# HW2.net
KiCad netlist of a schematic drawn in EAGLE
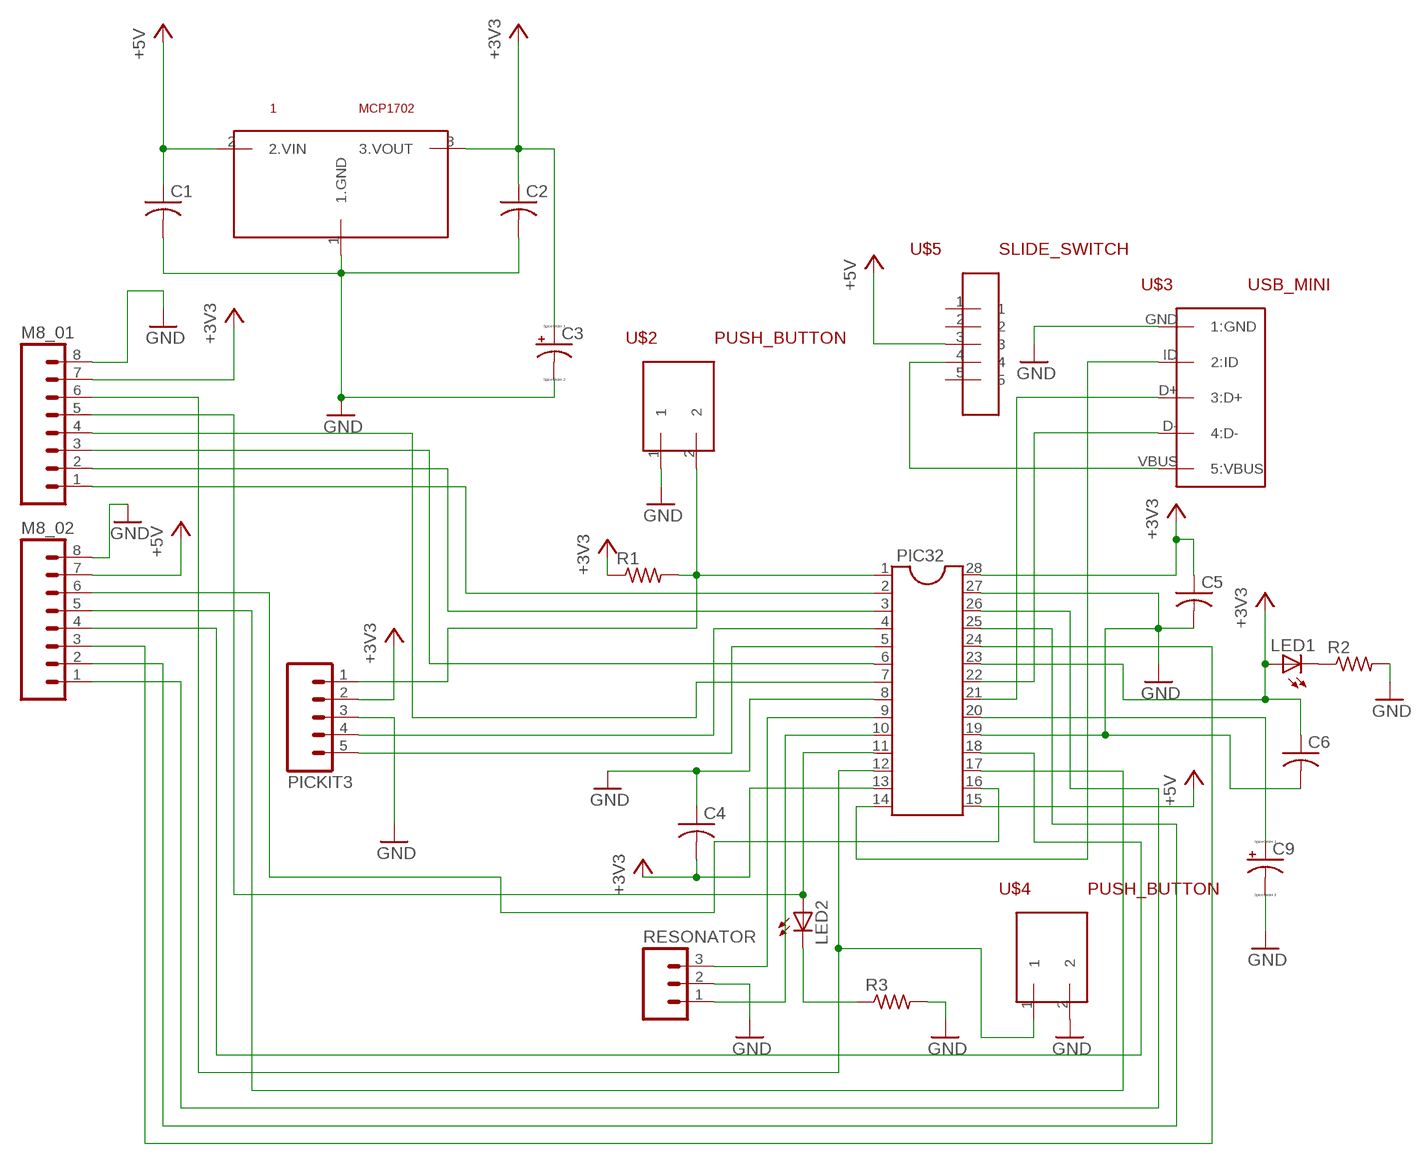
[diagram p0: schematic, sheet 1]

(export (version "E")
  (design (tool "Eeschema 10.0.6"))
  (components
    (comp (ref "1")
      (value "MCP1702")
      (footprint "eagle-import:TO92")
      (libsource (lib "eagle-import") (part "MCP1702"))
    )
    (comp (ref "C1")
      (value "C-US025-025X050")
      (footprint "eagle-import:C025-025X050")
      (libsource (lib "eagle-import") (part "C-US025-025X050"))
    )
    (comp (ref "C2")
      (value "C-US025-025X050")
      (footprint "eagle-import:C025-025X050")
      (libsource (lib "eagle-import") (part "C-US025-025X050"))
    )
    (comp (ref "C3")
      (value "CPOL-USE5-5")
      (footprint "eagle-import:E5-5")
      (libsource (lib "eagle-import") (part "CPOL-USE5-5"))
    )
    (comp (ref "C4")
      (value "C-US025-025X050")
      (footprint "eagle-import:C025-025X050")
      (libsource (lib "eagle-import") (part "C-US025-025X050"))
    )
    (comp (ref "C5")
      (value "C-US025-025X050")
      (footprint "eagle-import:C025-025X050")
      (libsource (lib "eagle-import") (part "C-US025-025X050"))
    )
    (comp (ref "C6")
      (value "C-US025-025X050")
      (footprint "eagle-import:C025-025X050")
      (libsource (lib "eagle-import") (part "C-US025-025X050"))
    )
    (comp (ref "C9")
      (value "CPOL-USE5-5")
      (footprint "eagle-import:E5-5")
      (libsource (lib "eagle-import") (part "CPOL-USE5-5"))
    )
    (comp (ref "LED1")
      (value "LED3MM")
      (footprint "eagle-import:LED3MM")
      (libsource (lib "eagle-import") (part "LED3MM"))
    )
    (comp (ref "LED2")
      (value "LED3MM")
      (footprint "eagle-import:LED3MM")
      (libsource (lib "eagle-import") (part "LED3MM"))
    )
    (comp (ref "M8_01")
      (value "M08")
      (footprint "eagle-import:1X08_ROUND")
      (libsource (lib "eagle-import") (part "M08"))
    )
    (comp (ref "M8_02")
      (value "M08")
      (footprint "eagle-import:1X08_ROUND")
      (libsource (lib "eagle-import") (part "M08"))
    )
    (comp (ref "PIC32")
      (value "DIL28-3")
      (footprint "eagle-import:DIL28-3")
      (libsource (lib "eagle-import") (part "DIL28-3"))
    )
    (comp (ref "PICKIT3")
      (value "M05PTH")
      (footprint "eagle-import:1X05")
      (libsource (lib "eagle-import") (part "M05PTH"))
    )
    (comp (ref "R1")
      (value "R-US_0207/10")
      (footprint "eagle-import:0207_10")
      (libsource (lib "eagle-import") (part "R-US_0207/10"))
    )
    (comp (ref "R2")
      (value "R-US_0207/10")
      (footprint "eagle-import:0207_10")
      (libsource (lib "eagle-import") (part "R-US_0207/10"))
    )
    (comp (ref "R3")
      (value "R-US_0207/10")
      (footprint "eagle-import:0207_10")
      (libsource (lib "eagle-import") (part "R-US_0207/10"))
    )
    (comp (ref "RESONATOR")
      (value "M03PTH")
      (footprint "eagle-import:1X03")
      (libsource (lib "eagle-import") (part "M03PTH"))
    )
    (comp (ref "U$2")
      (value "PUSH_BUTTON")
      (footprint "eagle-import:1X02_NO_SILK")
      (libsource (lib "eagle-import") (part "PUSH_BUTTON"))
    )
    (comp (ref "U$3")
      (value "USB_MINI")
      (footprint "eagle-import:USB-MB-H")
      (libsource (lib "eagle-import") (part "USB_MINI"))
    )
    (comp (ref "U$4")
      (value "PUSH_BUTTON")
      (footprint "eagle-import:1X02_NO_SILK")
      (libsource (lib "eagle-import") (part "PUSH_BUTTON"))
    )
    (comp (ref "U$5")
      (value "SLIDE_SWITCH")
      (footprint "eagle-import:1X05")
      (libsource (lib "eagle-import") (part "SLIDE_SWITCH"))
    )
  )
  (nets
    (net (code "1") (name "+3V3") (class "Default")
      (node (ref "1") (pin "3") (pinfunction "3.VOUT_3") (pintype "bidirectional"))
      (node (ref "C2") (pin "1") (pinfunction "1_1") (pintype "passive"))
      (node (ref "C3") (pin "+") (pinfunction "+_+") (pintype "passive"))
      (node (ref "C4") (pin "2") (pinfunction "2_2") (pintype "passive"))
      (node (ref "C5") (pin "1") (pinfunction "1_1") (pintype "passive"))
      (node (ref "C6") (pin "1") (pinfunction "1_1") (pintype "passive"))
      (node (ref "LED1") (pin "A") (pinfunction "A_A") (pintype "passive"))
      (node (ref "M8_01") (pin "7") (pinfunction "7_7") (pintype "passive"))
      (node (ref "PIC32") (pin "13") (pinfunction "13_13") (pintype "passive"))
      (node (ref "PIC32") (pin "23") (pinfunction "23_23") (pintype "passive"))
      (node (ref "PIC32") (pin "28") (pinfunction "28_28") (pintype "passive"))
      (node (ref "PICKIT3") (pin "2") (pinfunction "2_2") (pintype "passive"))
      (node (ref "R1") (pin "1") (pinfunction "1_1") (pintype "passive"))
    )
    (net (code "2") (name "+5V") (class "Default")
      (node (ref "1") (pin "2") (pinfunction "2.VIN_2") (pintype "bidirectional"))
      (node (ref "C1") (pin "1") (pinfunction "1_1") (pintype "passive"))
      (node (ref "M8_02") (pin "7") (pinfunction "7_7") (pintype "passive"))
      (node (ref "PIC32") (pin "15") (pinfunction "15_15") (pintype "passive"))
      (node (ref "U$5") (pin "3") (pinfunction "3_3") (pintype "bidirectional"))
    )
    (net (code "3") (name "GND") (class "Default")
      (node (ref "1") (pin "1") (pinfunction "1.GND_1") (pintype "bidirectional"))
      (node (ref "C1") (pin "2") (pinfunction "2_2") (pintype "passive"))
      (node (ref "C2") (pin "2") (pinfunction "2_2") (pintype "passive"))
      (node (ref "C3") (pin "-") (pinfunction "-_-") (pintype "passive"))
      (node (ref "C4") (pin "1") (pinfunction "1_1") (pintype "passive"))
      (node (ref "C5") (pin "2") (pinfunction "2_2") (pintype "passive"))
      (node (ref "C6") (pin "2") (pinfunction "2_2") (pintype "passive"))
      (node (ref "C9") (pin "-") (pinfunction "-_-") (pintype "passive"))
      (node (ref "M8_01") (pin "8") (pinfunction "8_8") (pintype "passive"))
      (node (ref "M8_02") (pin "8") (pinfunction "8_8") (pintype "passive"))
      (node (ref "PIC32") (pin "19") (pinfunction "19_19") (pintype "passive"))
      (node (ref "PIC32") (pin "27") (pinfunction "27_27") (pintype "passive"))
      (node (ref "PIC32") (pin "8") (pinfunction "8_8") (pintype "passive"))
      (node (ref "PICKIT3") (pin "3") (pinfunction "3_3") (pintype "passive"))
      (node (ref "R2") (pin "2") (pinfunction "2_2") (pintype "passive"))
      (node (ref "R3") (pin "2") (pinfunction "2_2") (pintype "passive"))
      (node (ref "RESONATOR") (pin "2") (pinfunction "2_2") (pintype "passive"))
      (node (ref "U$2") (pin "1") (pinfunction "1_1") (pintype "bidirectional"))
      (node (ref "U$3") (pin "GND") (pinfunction "1:GND_GND") (pintype "bidirectional"))
      (node (ref "U$4") (pin "2") (pinfunction "2_2") (pintype "bidirectional"))
    )
    (net (code "4") (name "Net-(C9-Pad+)") (class "Default")
      (node (ref "C9") (pin "+") (pinfunction "+_+") (pintype "passive"))
      (node (ref "PIC32") (pin "20") (pinfunction "20_20") (pintype "passive"))
    )
    (net (code "5") (name "Net-(LED1-C)") (class "Default")
      (node (ref "LED1") (pin "K") (pinfunction "C_K") (pintype "passive"))
      (node (ref "R2") (pin "1") (pinfunction "1_1") (pintype "passive"))
    )
    (net (code "6") (name "Net-(LED2-C)") (class "Default")
      (node (ref "LED2") (pin "K") (pinfunction "C_K") (pintype "passive"))
      (node (ref "R3") (pin "1") (pinfunction "1_1") (pintype "passive"))
    )
    (net (code "7") (name "Net-(LED2-PadA)") (class "Default")
      (node (ref "LED2") (pin "A") (pinfunction "A_A") (pintype "passive"))
      (node (ref "M8_01") (pin "5") (pinfunction "5_5") (pintype "passive"))
      (node (ref "PIC32") (pin "11") (pinfunction "11_11") (pintype "passive"))
    )
    (net (code "8") (name "Net-(M8_01-Pad2)") (class "Default")
      (node (ref "M8_01") (pin "2") (pinfunction "2_2") (pintype "passive"))
      (node (ref "PIC32") (pin "3") (pinfunction "3_3") (pintype "passive"))
    )
    (net (code "9") (name "Net-(M8_01-Pad3)") (class "Default")
      (node (ref "M8_01") (pin "3") (pinfunction "3_3") (pintype "passive"))
      (node (ref "PIC32") (pin "6") (pinfunction "6_6") (pintype "passive"))
    )
    (net (code "10") (name "Net-(M8_01-Pad4)") (class "Default")
      (node (ref "M8_01") (pin "4") (pinfunction "4_4") (pintype "passive"))
      (node (ref "PIC32") (pin "7") (pinfunction "7_7") (pintype "passive"))
    )
    (net (code "11") (name "Net-(M8_01-Pad6)") (class "Default")
      (node (ref "M8_01") (pin "6") (pinfunction "6_6") (pintype "passive"))
      (node (ref "PIC32") (pin "12") (pinfunction "12_12") (pintype "passive"))
      (node (ref "U$4") (pin "1") (pinfunction "1_1") (pintype "bidirectional"))
    )
    (net (code "12") (name "Net-(M8_02-Pad1)") (class "Default")
      (node (ref "M8_02") (pin "1") (pinfunction "1_1") (pintype "passive"))
      (node (ref "PIC32") (pin "26") (pinfunction "26_26") (pintype "passive"))
    )
    (net (code "13") (name "Net-(M8_02-Pad2)") (class "Default")
      (node (ref "M8_02") (pin "2") (pinfunction "2_2") (pintype "passive"))
      (node (ref "PIC32") (pin "25") (pinfunction "25_25") (pintype "passive"))
    )
    (net (code "14") (name "Net-(M8_02-Pad3)") (class "Default")
      (node (ref "M8_02") (pin "3") (pinfunction "3_3") (pintype "passive"))
      (node (ref "PIC32") (pin "24") (pinfunction "24_24") (pintype "passive"))
    )
    (net (code "15") (name "Net-(M8_02-Pad4)") (class "Default")
      (node (ref "M8_02") (pin "4") (pinfunction "4_4") (pintype "passive"))
      (node (ref "PIC32") (pin "18") (pinfunction "18_18") (pintype "passive"))
    )
    (net (code "16") (name "Net-(M8_02-Pad5)") (class "Default")
      (node (ref "M8_02") (pin "5") (pinfunction "5_5") (pintype "passive"))
      (node (ref "PIC32") (pin "17") (pinfunction "17_17") (pintype "passive"))
    )
    (net (code "17") (name "Net-(M8_02-Pad6)") (class "Default")
      (node (ref "M8_02") (pin "6") (pinfunction "6_6") (pintype "passive"))
      (node (ref "PIC32") (pin "16") (pinfunction "16_16") (pintype "passive"))
    )
    (net (code "18") (name "Net-(PIC32-1:~{MCLR})") (class "Default")
      (node (ref "PIC32") (pin "1") (pinfunction "1:~{MCLR}_1") (pintype "passive"))
      (node (ref "PICKIT3") (pin "1") (pinfunction "1_1") (pintype "passive"))
      (node (ref "R1") (pin "2") (pinfunction "2_2") (pintype "passive"))
      (node (ref "U$2") (pin "2") (pinfunction "2_2") (pintype "bidirectional"))
    )
    (net (code "19") (name "Net-(PIC32-2:A0)") (class "Default")
      (node (ref "M8_01") (pin "1") (pinfunction "1_1") (pintype "passive"))
      (node (ref "PIC32") (pin "2") (pinfunction "2:A0_2") (pintype "passive"))
    )
    (net (code "20") (name "Net-(PIC32-Pad4)") (class "Default")
      (node (ref "PIC32") (pin "4") (pinfunction "4_4") (pintype "passive"))
      (node (ref "PICKIT3") (pin "4") (pinfunction "4_4") (pintype "passive"))
    )
    (net (code "21") (name "Net-(PIC32-Pad5)") (class "Default")
      (node (ref "PIC32") (pin "5") (pinfunction "5_5") (pintype "passive"))
      (node (ref "PICKIT3") (pin "5") (pinfunction "5_5") (pintype "passive"))
    )
    (net (code "22") (name "Net-(PIC32-Pad9)") (class "Default")
      (node (ref "PIC32") (pin "9") (pinfunction "9_9") (pintype "passive"))
      (node (ref "RESONATOR") (pin "3") (pinfunction "3_3") (pintype "passive"))
    )
    (net (code "23") (name "Net-(PIC32-Pad10)") (class "Default")
      (node (ref "PIC32") (pin "10") (pinfunction "10_10") (pintype "passive"))
      (node (ref "RESONATOR") (pin "1") (pinfunction "1_1") (pintype "passive"))
    )
    (net (code "24") (name "Net-(U$3-2:ID)") (class "Default")
      (node (ref "PIC32") (pin "14") (pinfunction "14_14") (pintype "passive"))
      (node (ref "U$3") (pin "ID") (pinfunction "2:ID_ID") (pintype "bidirectional"))
    )
    (net (code "25") (name "Net-(U$3-3:D+)") (class "Default")
      (node (ref "PIC32") (pin "21") (pinfunction "21_21") (pintype "passive"))
      (node (ref "U$3") (pin "D+") (pinfunction "3:D+_D+") (pintype "bidirectional"))
    )
    (net (code "26") (name "Net-(U$3-4:D-)") (class "Default")
      (node (ref "PIC32") (pin "22") (pinfunction "22_22") (pintype "passive"))
      (node (ref "U$3") (pin "D-") (pinfunction "4:D-_D-") (pintype "bidirectional"))
    )
    (net (code "27") (name "Net-(U$3-5:VBUS)") (class "Default")
      (node (ref "U$3") (pin "VBUS") (pinfunction "5:VBUS_VBUS") (pintype "bidirectional"))
      (node (ref "U$5") (pin "4") (pinfunction "4_4") (pintype "bidirectional"))
    )
    (net (code "28") (name "unconnected-(U$5-Pad1)") (class "Default")
      (node (ref "U$5") (pin "1") (pinfunction "1_1") (pintype "bidirectional"))
    )
    (net (code "29") (name "unconnected-(U$5-Pad2)") (class "Default")
      (node (ref "U$5") (pin "2") (pinfunction "2_2") (pintype "bidirectional"))
    )
    (net (code "30") (name "unconnected-(U$5-Pad5)") (class "Default")
      (node (ref "U$5") (pin "5") (pinfunction "5_5") (pintype "bidirectional"))
    )
  )
)
